# IRBeaconRev4.net
KiCad netlist of a schematic drawn in EAGLE
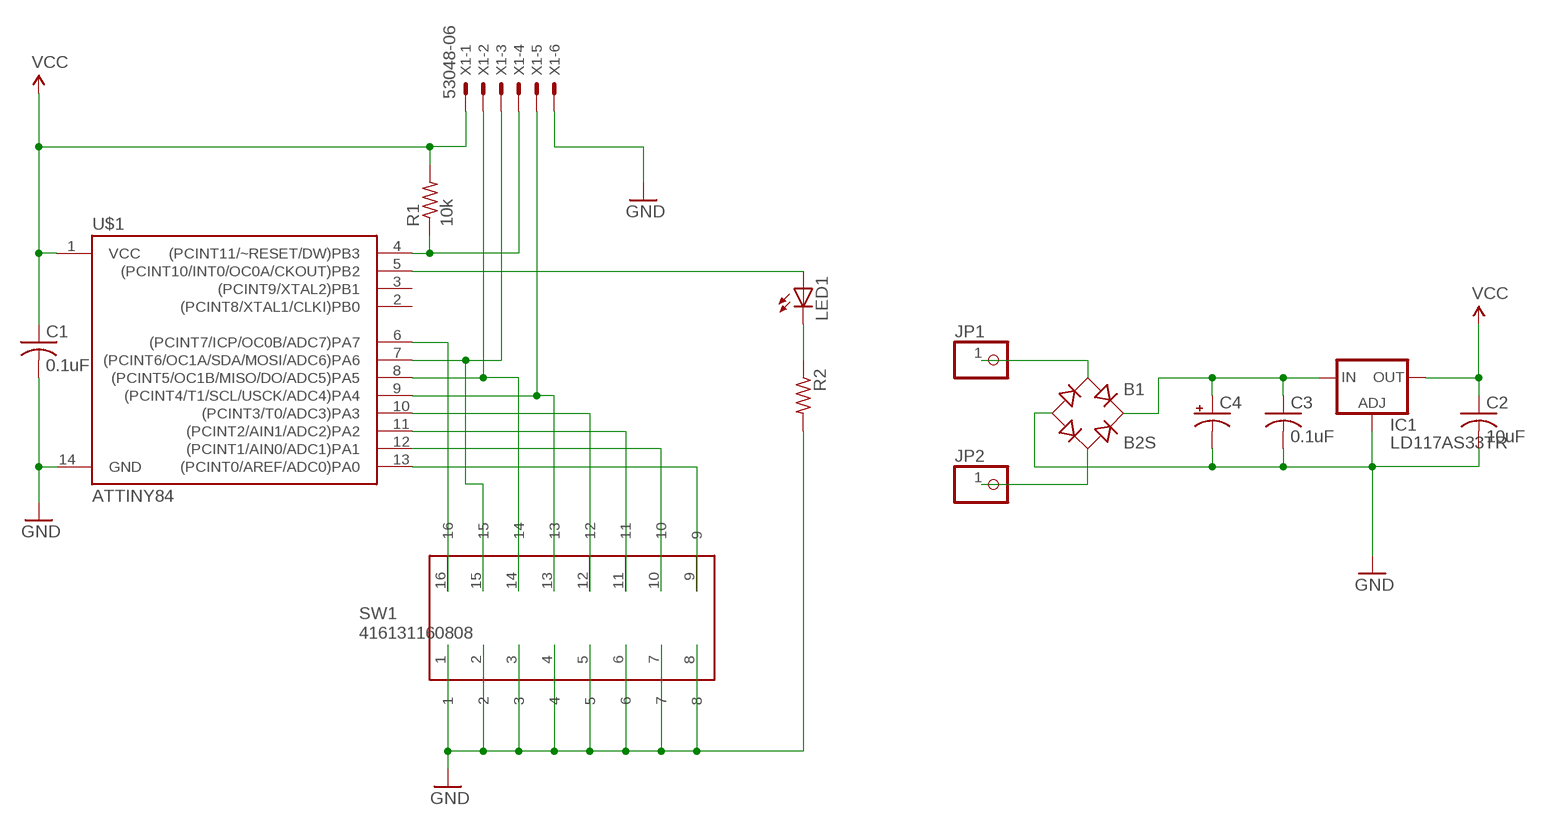
[diagram p0: schematic, sheet 1]

(export (version "E")
  (design (tool "Eeschema 10.0.6"))
  (components
    (comp (ref "B1")
      (value "B2S")
      (footprint "eagle-import:MBS")
      (libsource (lib "eagle-import") (part "BS2"))
    )
    (comp (ref "C1")
      (value "0.1uF")
      (footprint "eagle-import:C0805")
      (libsource (lib "eagle-import") (part "C-USC0805"))
    )
    (comp (ref "C2")
      (value "10uF")
      (footprint "eagle-import:C0805")
      (libsource (lib "eagle-import") (part "C-USC0805"))
    )
    (comp (ref "C3")
      (value "0.1uF")
      (footprint "eagle-import:C0805")
      (libsource (lib "eagle-import") (part "C-USC0805"))
    )
    (comp (ref "C4")
      (value "CAP_POLPTH4")
      (footprint "eagle-import:CPOL-RADIAL-1000UF-25V")
      (libsource (lib "eagle-import") (part "CAP_POLPTH4"))
    )
    (comp (ref "IC1")
      (value "LD117AS33TR")
      (footprint "eagle-import:SOT223")
      (libsource (lib "eagle-import") (part "LD117A?S33TR"))
    )
    (comp (ref "JP1")
      (value "PINHD-1X1")
      (footprint "eagle-import:1X01")
      (libsource (lib "eagle-import") (part "PINHD-1X1"))
    )
    (comp (ref "JP2")
      (value "PINHD-1X1")
      (footprint "eagle-import:1X01")
      (libsource (lib "eagle-import") (part "PINHD-1X1"))
    )
    (comp (ref "LED1")
      (value "LEDCHIPLED_1206")
      (footprint "eagle-import:CHIPLED_1206")
      (libsource (lib "eagle-import") (part "LEDCHIPLED_1206"))
    )
    (comp (ref "R1")
      (value "10k")
      (footprint "eagle-import:R0805")
      (libsource (lib "eagle-import") (part "R-US_R0805"))
    )
    (comp (ref "R2")
      (value "R-US_R0805")
      (footprint "eagle-import:R0805")
      (libsource (lib "eagle-import") (part "R-US_R0805"))
    )
    (comp (ref "SW1")
      (value "416131160808")
      (footprint "eagle-import:416131160808")
      (libsource (lib "eagle-import") (part "416131160808"))
    )
    (comp (ref "U$1")
      (value "ATTINY84")
      (footprint "eagle-import:SO14")
      (libsource (lib "eagle-import") (part "ATTINY84"))
    )
    (comp (ref "X1")
      (value "53048-06")
      (footprint "eagle-import:53048-06")
      (fields (field (name "MF") "WALDOM/MOLEX") (field (name "MPN") "53048-0610"))
      (libsource (lib "eagle-import") (part "53?-06048"))
    )
  )
  (nets
    (net (code "1") (name "GND") (class "Default")
      (node (ref "B1") (pin "-") (pinfunction "-_-") (pintype "passive"))
      (node (ref "C1") (pin "2") (pinfunction "2_2") (pintype "passive"))
      (node (ref "C2") (pin "2") (pinfunction "2_2") (pintype "passive"))
      (node (ref "C3") (pin "2") (pinfunction "2_2") (pintype "passive"))
      (node (ref "C4") (pin "2") (pinfunction "-_2") (pintype "passive"))
      (node (ref "IC1") (pin "1") (pinfunction "ADJ_1") (pintype "input"))
      (node (ref "R2") (pin "2") (pinfunction "2_2") (pintype "passive"))
      (node (ref "SW1") (pin "1") (pinfunction "1_1") (pintype "bidirectional"))
      (node (ref "SW1") (pin "2") (pinfunction "2_2") (pintype "bidirectional"))
      (node (ref "SW1") (pin "3") (pinfunction "3_3") (pintype "bidirectional"))
      (node (ref "SW1") (pin "4") (pinfunction "4_4") (pintype "bidirectional"))
      (node (ref "SW1") (pin "5") (pinfunction "5_5") (pintype "bidirectional"))
      (node (ref "SW1") (pin "6") (pinfunction "6_6") (pintype "bidirectional"))
      (node (ref "SW1") (pin "7") (pinfunction "7_7") (pintype "bidirectional"))
      (node (ref "SW1") (pin "8") (pinfunction "8_8") (pintype "bidirectional"))
      (node (ref "U$1") (pin "14") (pinfunction "GND_14") (pintype "bidirectional"))
      (node (ref "X1") (pin "6") (pinfunction "S_6") (pintype "passive"))
    )
    (net (code "2") (name "Net-(B1-PadAC1)") (class "Default")
      (node (ref "B1") (pin "AC1") (pinfunction "AC1_AC1") (pintype "passive"))
      (node (ref "JP1") (pin "1") (pinfunction "1_1") (pintype "passive"))
    )
    (net (code "3") (name "Net-(B1-PadAC2)") (class "Default")
      (node (ref "B1") (pin "AC2") (pinfunction "AC2_AC2") (pintype "passive"))
      (node (ref "JP2") (pin "1") (pinfunction "1_1") (pintype "passive"))
    )
    (net (code "4") (name "Net-(C4-+)") (class "Default")
      (node (ref "B1") (pin "+") (pinfunction "+_+") (pintype "passive"))
      (node (ref "C3") (pin "1") (pinfunction "1_1") (pintype "passive"))
      (node (ref "C4") (pin "1") (pinfunction "+_1") (pintype "passive"))
      (node (ref "IC1") (pin "3") (pinfunction "IN_3") (pintype "input"))
    )
    (net (code "5") (name "Net-(LED1-PadC)") (class "Default")
      (node (ref "LED1") (pin "C") (pinfunction "C_C") (pintype "passive"))
      (node (ref "R2") (pin "1") (pinfunction "1_1") (pintype "passive"))
    )
    (net (code "6") (name "Net-(U$1-(PCINT0{slash}AREF{slash}ADC0)PA0)") (class "Default")
      (node (ref "SW1") (pin "9") (pinfunction "9_9") (pintype "bidirectional"))
      (node (ref "U$1") (pin "13") (pinfunction "(PCINT0/AREF/ADC0)PA0_13") (pintype "bidirectional"))
    )
    (net (code "7") (name "Net-(U$1-(PCINT1{slash}AIN0{slash}ADC1)PA1)") (class "Default")
      (node (ref "SW1") (pin "10") (pinfunction "10_10") (pintype "bidirectional"))
      (node (ref "U$1") (pin "12") (pinfunction "(PCINT1/AIN0/ADC1)PA1_12") (pintype "bidirectional"))
    )
    (net (code "8") (name "Net-(U$1-(PCINT2{slash}AIN1{slash}ADC2)PA2)") (class "Default")
      (node (ref "SW1") (pin "11") (pinfunction "11_11") (pintype "bidirectional"))
      (node (ref "U$1") (pin "11") (pinfunction "(PCINT2/AIN1/ADC2)PA2_11") (pintype "bidirectional"))
    )
    (net (code "9") (name "Net-(U$1-(PCINT3{slash}T0{slash}ADC3)PA3)") (class "Default")
      (node (ref "SW1") (pin "12") (pinfunction "12_12") (pintype "bidirectional"))
      (node (ref "U$1") (pin "10") (pinfunction "(PCINT3/T0/ADC3)PA3_10") (pintype "bidirectional"))
    )
    (net (code "10") (name "Net-(U$1-(PCINT4{slash}T1{slash}SCL{slash}USCK{slash}ADC4)PA4)") (class "Default")
      (node (ref "SW1") (pin "13") (pinfunction "13_13") (pintype "bidirectional"))
      (node (ref "U$1") (pin "9") (pinfunction "(PCINT4/T1/SCL/USCK/ADC4)PA4_9") (pintype "bidirectional"))
      (node (ref "X1") (pin "5") (pinfunction "S_5") (pintype "passive"))
    )
    (net (code "11") (name "Net-(U$1-(PCINT5{slash}OC1B{slash}MISO{slash}DO{slash}ADC5)PA5)") (class "Default")
      (node (ref "SW1") (pin "14") (pinfunction "14_14") (pintype "bidirectional"))
      (node (ref "U$1") (pin "8") (pinfunction "(PCINT5/OC1B/MISO/DO/ADC5)PA5_8") (pintype "bidirectional"))
      (node (ref "X1") (pin "2") (pinfunction "S_2") (pintype "passive"))
    )
    (net (code "12") (name "Net-(U$1-(PCINT6{slash}OC1A{slash}SDA{slash}MOSI{slash}ADC6)PA6)") (class "Default")
      (node (ref "SW1") (pin "15") (pinfunction "15_15") (pintype "bidirectional"))
      (node (ref "U$1") (pin "7") (pinfunction "(PCINT6/OC1A/SDA/MOSI/ADC6)PA6_7") (pintype "bidirectional"))
      (node (ref "X1") (pin "3") (pinfunction "S_3") (pintype "passive"))
    )
    (net (code "13") (name "Net-(U$1-(PCINT7{slash}ICP{slash}OC0B{slash}ADC7)PA7)") (class "Default")
      (node (ref "SW1") (pin "16") (pinfunction "16_16") (pintype "bidirectional"))
      (node (ref "U$1") (pin "6") (pinfunction "(PCINT7/ICP/OC0B/ADC7)PA7_6") (pintype "bidirectional"))
    )
    (net (code "14") (name "Net-(U$1-(PCINT10{slash}INT0{slash}OC0A{slash}CKOUT)PB2)") (class "Default")
      (node (ref "LED1") (pin "A") (pinfunction "A_A") (pintype "passive"))
      (node (ref "U$1") (pin "5") (pinfunction "(PCINT10/INT0/OC0A/CKOUT)PB2_5") (pintype "bidirectional"))
    )
    (net (code "15") (name "Net-(U$1-(PCINT11{slash}~{RESET{slash}DW})PB3)") (class "Default")
      (node (ref "R1") (pin "1") (pinfunction "1_1") (pintype "passive"))
      (node (ref "U$1") (pin "4") (pinfunction "(PCINT11/~{RESET/DW})PB3_4") (pintype "bidirectional"))
      (node (ref "X1") (pin "4") (pinfunction "S_4") (pintype "passive"))
    )
    (net (code "16") (name "VCC") (class "Default")
      (node (ref "C1") (pin "1") (pinfunction "1_1") (pintype "passive"))
      (node (ref "C2") (pin "1") (pinfunction "1_1") (pintype "passive"))
      (node (ref "IC1") (pin "4") (pinfunction "OUT_4") (pintype "passive"))
      (node (ref "R1") (pin "2") (pinfunction "2_2") (pintype "passive"))
      (node (ref "U$1") (pin "1") (pinfunction "VCC_1") (pintype "bidirectional"))
      (node (ref "X1") (pin "1") (pinfunction "S_1") (pintype "passive"))
    )
    (net (code "17") (name "unconnected-(U$1-(PCINT8{slash}XTAL1{slash}CLKI)PB0-Pad2)") (class "Default")
      (node (ref "U$1") (pin "2") (pinfunction "(PCINT8/XTAL1/CLKI)PB0_2") (pintype "bidirectional"))
    )
    (net (code "18") (name "unconnected-(U$1-(PCINT9{slash}XTAL2)PB1-Pad3)") (class "Default")
      (node (ref "U$1") (pin "3") (pinfunction "(PCINT9/XTAL2)PB1_3") (pintype "bidirectional"))
    )
  )
)
